# 06_CAN_Interface.net
KiCad netlist of a schematic drawn in Altium Designer
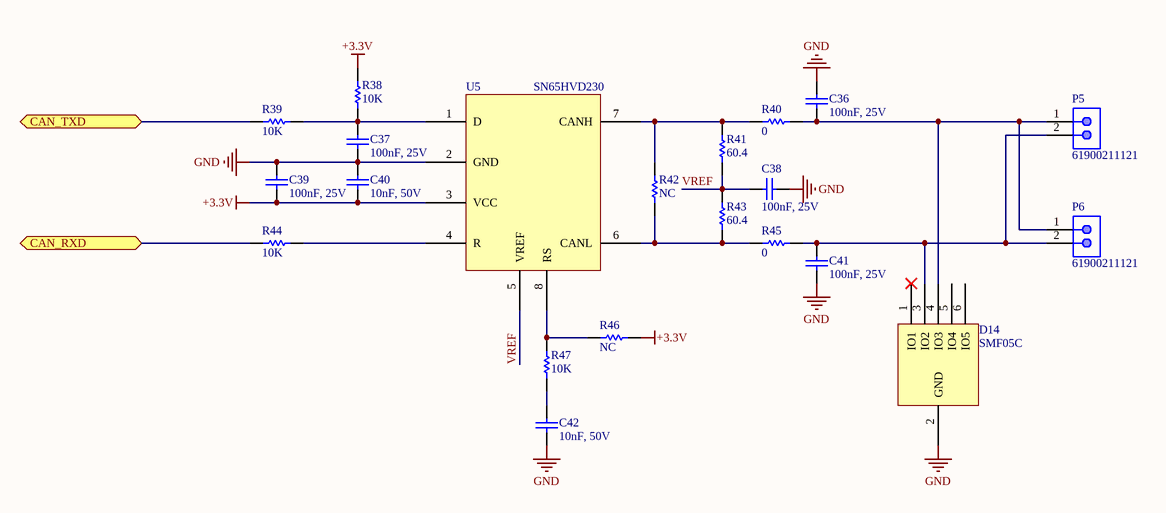
[diagram p0: 06_CAN_Interface.SchDoc]

(export (version "E")
  (design (tool "Eeschema 10.0.6"))
  (components
    (comp (ref "C36")
      (value "100nF, 25V")
      (footprint "WCAP-CSGP_0603_H=0.8mm_Reflow")
      (description "WCAP-CSGP Multilayer Ceramic Chip Capacitor, General Purpose, size 0603, X7R, 100nF, 25V")
      (fields
        (field (name "MANUFACTURER PART NUMBER") "885012206071")
        (field (name "MANUFACTURER") "Wurth Elektronik")
      )
      (libsource (lib "Altium_WCAP-CSGP (rev20a)") (part "885012206071"))
    )
    (comp (ref "C37")
      (value "100nF, 25V")
      (footprint "WCAP-CSGP_0603_H=0.8mm_Reflow")
      (description "WCAP-CSGP Multilayer Ceramic Chip Capacitor, General Purpose, size 0603, X7R, 100nF, 25V")
      (fields
        (field (name "MANUFACTURER PART NUMBER") "885012206071")
        (field (name "MANUFACTURER") "Wurth Elektronik")
      )
      (libsource (lib "Altium_WCAP-CSGP (rev20a)") (part "885012206071"))
    )
    (comp (ref "C38")
      (value "100nF, 25V")
      (footprint "WCAP-CSGP_0603_H=0.8mm_Reflow")
      (description "WCAP-CSGP Multilayer Ceramic Chip Capacitor, General Purpose, size 0603, X7R, 100nF, 25V")
      (fields
        (field (name "MANUFACTURER PART NUMBER") "885012206071")
        (field (name "MANUFACTURER") "Wurth Elektronik")
      )
      (libsource (lib "Altium_WCAP-CSGP (rev20a)") (part "885012206071"))
    )
    (comp (ref "C39")
      (value "100nF, 25V")
      (footprint "WCAP-CSGP_0603_H=0.8mm_Reflow")
      (description "WCAP-CSGP Multilayer Ceramic Chip Capacitor, General Purpose, size 0603, X7R, 100nF, 25V")
      (fields
        (field (name "MANUFACTURER PART NUMBER") "885012206071")
        (field (name "MANUFACTURER") "Wurth Elektronik")
      )
      (libsource (lib "Altium_WCAP-CSGP (rev20a)") (part "885012206071"))
    )
    (comp (ref "C40")
      (value "10nF, 50V")
      (footprint "WCAP-CSGP_0603_H=0.8mm_Reflow")
      (description "WCAP-CSGP Multilayer Ceramic Chip Capacitor, General Purpose, size 0603, X7R, 10nF, 50V")
      (fields
        (field (name "MANUFACTURER PART NUMBER") "885012206089")
        (field (name "MANUFACTURER") "Wurth Elektronik")
      )
      (libsource (lib "Altium_WCAP-CSGP (rev20a)") (part "885012206089"))
    )
    (comp (ref "C41")
      (value "100nF, 25V")
      (footprint "WCAP-CSGP_0603_H=0.8mm_Reflow")
      (description "WCAP-CSGP Multilayer Ceramic Chip Capacitor, General Purpose, size 0603, X7R, 100nF, 25V")
      (fields
        (field (name "MANUFACTURER PART NUMBER") "885012206071")
        (field (name "MANUFACTURER") "Wurth Elektronik")
      )
      (libsource (lib "Altium_WCAP-CSGP (rev20a)") (part "885012206071"))
    )
    (comp (ref "C42")
      (value "10nF, 50V")
      (footprint "WCAP-CSGP_0603_H=0.8mm_Reflow")
      (description "WCAP-CSGP Multilayer Ceramic Chip Capacitor, General Purpose, size 0603, X7R, 10nF, 50V")
      (fields
        (field (name "MANUFACTURER PART NUMBER") "885012206089")
        (field (name "MANUFACTURER") "Wurth Elektronik")
      )
      (libsource (lib "Altium_WCAP-CSGP (rev20a)") (part "885012206089"))
    )
    (comp (ref "D14")
      (value "SMF05C")
      (footprint "SOT65P210X110-6N")
      (libsource (lib "MiclsLib") (part "SMF05C"))
    )
    (comp (ref "P5")
      (value "61900211121")
      (footprint "61900211121")
      (description "WR-WTB THT Male Vertical Locking Header, pitch 2.54mm, 2p")
      (fields (field (name "PUBLISHER") "Wurth Elektronik"))
      (libsource (lib "653008114822_Altium_WR-WTB_rev20a") (part "61900211121"))
    )
    (comp (ref "P6")
      (value "61900211121")
      (footprint "61900211121")
      (description "WR-WTB THT Male Vertical Locking Header, pitch 2.54mm, 2p")
      (fields (field (name "PUBLISHER") "Wurth Elektronik"))
      (libsource (lib "653008114822_Altium_WR-WTB_rev20a") (part "61900211121"))
    )
    (comp (ref "R38")
      (value "10K")
      (footprint "RES-SM-0603")
      (description "Resistor")
      (fields (field (name "Comment") "RESISTOR SMD"))
      (libsource (lib "PIF_Library") (part "RESISTOR SMD"))
    )
    (comp (ref "R39")
      (value "10K")
      (footprint "RES-SM-0603")
      (description "Resistor")
      (fields (field (name "Comment") "RESISTOR SMD"))
      (libsource (lib "PIF_Library") (part "RESISTOR SMD"))
    )
    (comp (ref "R40")
      (value "0")
      (footprint "RES-SM-0603")
      (description "Resistor")
      (fields (field (name "Comment") "RESISTOR SMD"))
      (libsource (lib "PIF_Library") (part "RESISTOR SMD"))
    )
    (comp (ref "R41")
      (value "60.4")
      (footprint "RES-SM-0603")
      (description "Resistor")
      (fields (field (name "Comment") "RESISTOR SMD"))
      (libsource (lib "PIF_Library") (part "RESISTOR SMD"))
    )
    (comp (ref "R42")
      (value "NC")
      (footprint "RES-SM-0603")
      (description "Resistor")
      (fields (field (name "Comment") "RESISTOR SMD"))
      (libsource (lib "PIF_Library") (part "RESISTOR SMD"))
    )
    (comp (ref "R43")
      (value "60.4")
      (footprint "RES-SM-0603")
      (description "Resistor")
      (fields (field (name "Comment") "RESISTOR SMD"))
      (libsource (lib "PIF_Library") (part "RESISTOR SMD"))
    )
    (comp (ref "R44")
      (value "10K")
      (footprint "RES-SM-0603")
      (description "Resistor")
      (fields (field (name "Comment") "RESISTOR SMD"))
      (libsource (lib "PIF_Library") (part "RESISTOR SMD"))
    )
    (comp (ref "R45")
      (value "0")
      (footprint "RES-SM-0603")
      (description "Resistor")
      (fields (field (name "Comment") "RESISTOR SMD"))
      (libsource (lib "PIF_Library") (part "RESISTOR SMD"))
    )
    (comp (ref "R46")
      (value "NC")
      (footprint "RES-SM-0603")
      (description "Resistor")
      (fields (field (name "Comment") "RESISTOR SMD"))
      (libsource (lib "PIF_Library") (part "RESISTOR SMD"))
    )
    (comp (ref "R47")
      (value "10K")
      (footprint "RES-SM-0603")
      (description "Resistor")
      (fields (field (name "Comment") "RESISTOR SMD"))
      (libsource (lib "PIF_Library") (part "RESISTOR SMD"))
    )
    (comp (ref "U5")
      (value "SN65HVD230")
      (footprint "SOIC127P600X175-8N")
      (libsource (lib "MiclsLib") (part "SN65HVD230"))
    )
  )
  (nets
    (net (code "1") (name "+3.3V") (class "Default")
      (node (ref "C39") (pin "1") (pinfunction "1_1") (pintype "passive"))
      (node (ref "C40") (pin "1") (pinfunction "1_1") (pintype "passive"))
      (node (ref "R38") (pin "2") (pinfunction "2_2") (pintype "passive"))
      (node (ref "R46") (pin "1") (pinfunction "1_1") (pintype "passive"))
      (node (ref "U5") (pin "3") (pinfunction "VCC_3") (pintype "passive"))
    )
    (net (code "2") (name "/CAN_RXD") (class "Default")
      (node (ref "R44") (pin "2") (pinfunction "2_2") (pintype "passive"))
    )
    (net (code "3") (name "/CAN_TXD") (class "Default")
      (node (ref "R39") (pin "2") (pinfunction "2_2") (pintype "passive"))
    )
    (net (code "4") (name "/VREF") (class "Default")
      (node (ref "C38") (pin "2") (pinfunction "2_2") (pintype "passive"))
      (node (ref "R41") (pin "2") (pinfunction "2_2") (pintype "passive"))
      (node (ref "R43") (pin "1") (pinfunction "1_1") (pintype "passive"))
      (node (ref "U5") (pin "5") (pinfunction "VREF_5") (pintype "passive"))
    )
    (net (code "5") (name "GND") (class "Default")
      (node (ref "C36") (pin "2") (pinfunction "2_2") (pintype "passive"))
      (node (ref "C37") (pin "1") (pinfunction "1_1") (pintype "passive"))
      (node (ref "C38") (pin "1") (pinfunction "1_1") (pintype "passive"))
      (node (ref "C39") (pin "2") (pinfunction "2_2") (pintype "passive"))
      (node (ref "C40") (pin "2") (pinfunction "2_2") (pintype "passive"))
      (node (ref "C41") (pin "1") (pinfunction "1_1") (pintype "passive"))
      (node (ref "C42") (pin "1") (pinfunction "1_1") (pintype "passive"))
      (node (ref "D14") (pin "2") (pinfunction "GND_2") (pintype "passive"))
      (node (ref "U5") (pin "2") (pinfunction "GND_2") (pintype "passive"))
    )
    (net (code "6") (name "Net-(C42-Pad2)") (class "Default")
      (node (ref "C42") (pin "2") (pinfunction "2_2") (pintype "passive"))
      (node (ref "R47") (pin "1") (pinfunction "1_1") (pintype "passive"))
    )
    (net (code "7") (name "Net-(D14-IO2)") (class "Default")
      (node (ref "C41") (pin "2") (pinfunction "2_2") (pintype "passive"))
      (node (ref "D14") (pin "3") (pinfunction "IO2_3") (pintype "passive"))
      (node (ref "P5") (pin "2") (pinfunction "2_2") (pintype "passive"))
      (node (ref "P6") (pin "2") (pinfunction "2_2") (pintype "passive"))
      (node (ref "R45") (pin "1") (pinfunction "1_1") (pintype "passive"))
    )
    (net (code "8") (name "Net-(D14-IO3)") (class "Default")
      (node (ref "C36") (pin "1") (pinfunction "1_1") (pintype "passive"))
      (node (ref "D14") (pin "4") (pinfunction "IO3_4") (pintype "passive"))
      (node (ref "P5") (pin "1") (pinfunction "1_1") (pintype "passive"))
      (node (ref "P6") (pin "1") (pinfunction "1_1") (pintype "passive"))
      (node (ref "R40") (pin "1") (pinfunction "1_1") (pintype "passive"))
    )
    (net (code "9") (name "Net-(U5-CANH)") (class "Default")
      (node (ref "R40") (pin "2") (pinfunction "2_2") (pintype "passive"))
      (node (ref "R41") (pin "1") (pinfunction "1_1") (pintype "passive"))
      (node (ref "R42") (pin "1") (pinfunction "1_1") (pintype "passive"))
      (node (ref "U5") (pin "7") (pinfunction "CANH_7") (pintype "passive"))
    )
    (net (code "10") (name "Net-(U5-CANL)") (class "Default")
      (node (ref "R42") (pin "2") (pinfunction "2_2") (pintype "passive"))
      (node (ref "R43") (pin "2") (pinfunction "2_2") (pintype "passive"))
      (node (ref "R45") (pin "2") (pinfunction "2_2") (pintype "passive"))
      (node (ref "U5") (pin "6") (pinfunction "CANL_6") (pintype "passive"))
    )
    (net (code "11") (name "Net-(U5-D)") (class "Default")
      (node (ref "C37") (pin "2") (pinfunction "2_2") (pintype "passive"))
      (node (ref "R38") (pin "1") (pinfunction "1_1") (pintype "passive"))
      (node (ref "R39") (pin "1") (pinfunction "1_1") (pintype "passive"))
      (node (ref "U5") (pin "1") (pinfunction "D_1") (pintype "passive"))
    )
    (net (code "12") (name "Net-(U5-R)") (class "Default")
      (node (ref "R44") (pin "1") (pinfunction "1_1") (pintype "passive"))
      (node (ref "U5") (pin "4") (pinfunction "R_4") (pintype "passive"))
    )
    (net (code "13") (name "Net-(U5-RS)") (class "Default")
      (node (ref "R46") (pin "2") (pinfunction "2_2") (pintype "passive"))
      (node (ref "R47") (pin "2") (pinfunction "2_2") (pintype "passive"))
      (node (ref "U5") (pin "8") (pinfunction "RS_8") (pintype "passive"))
    )
    (net (code "14") (name "unconnected-(D14-IO1-Pad1)") (class "Default")
      (node (ref "D14") (pin "1") (pinfunction "IO1_1") (pintype "passive+no_connect"))
    )
    (net (code "15") (name "unconnected-(D14-IO4-Pad5)") (class "Default")
      (node (ref "D14") (pin "5") (pinfunction "IO4_5") (pintype "passive"))
    )
    (net (code "16") (name "unconnected-(D14-IO5-Pad6)") (class "Default")
      (node (ref "D14") (pin "6") (pinfunction "IO5_6") (pintype "passive"))
    )
  )
)
